# DVI-I.net
KiCad netlist of a schematic drawn in Altium Designer
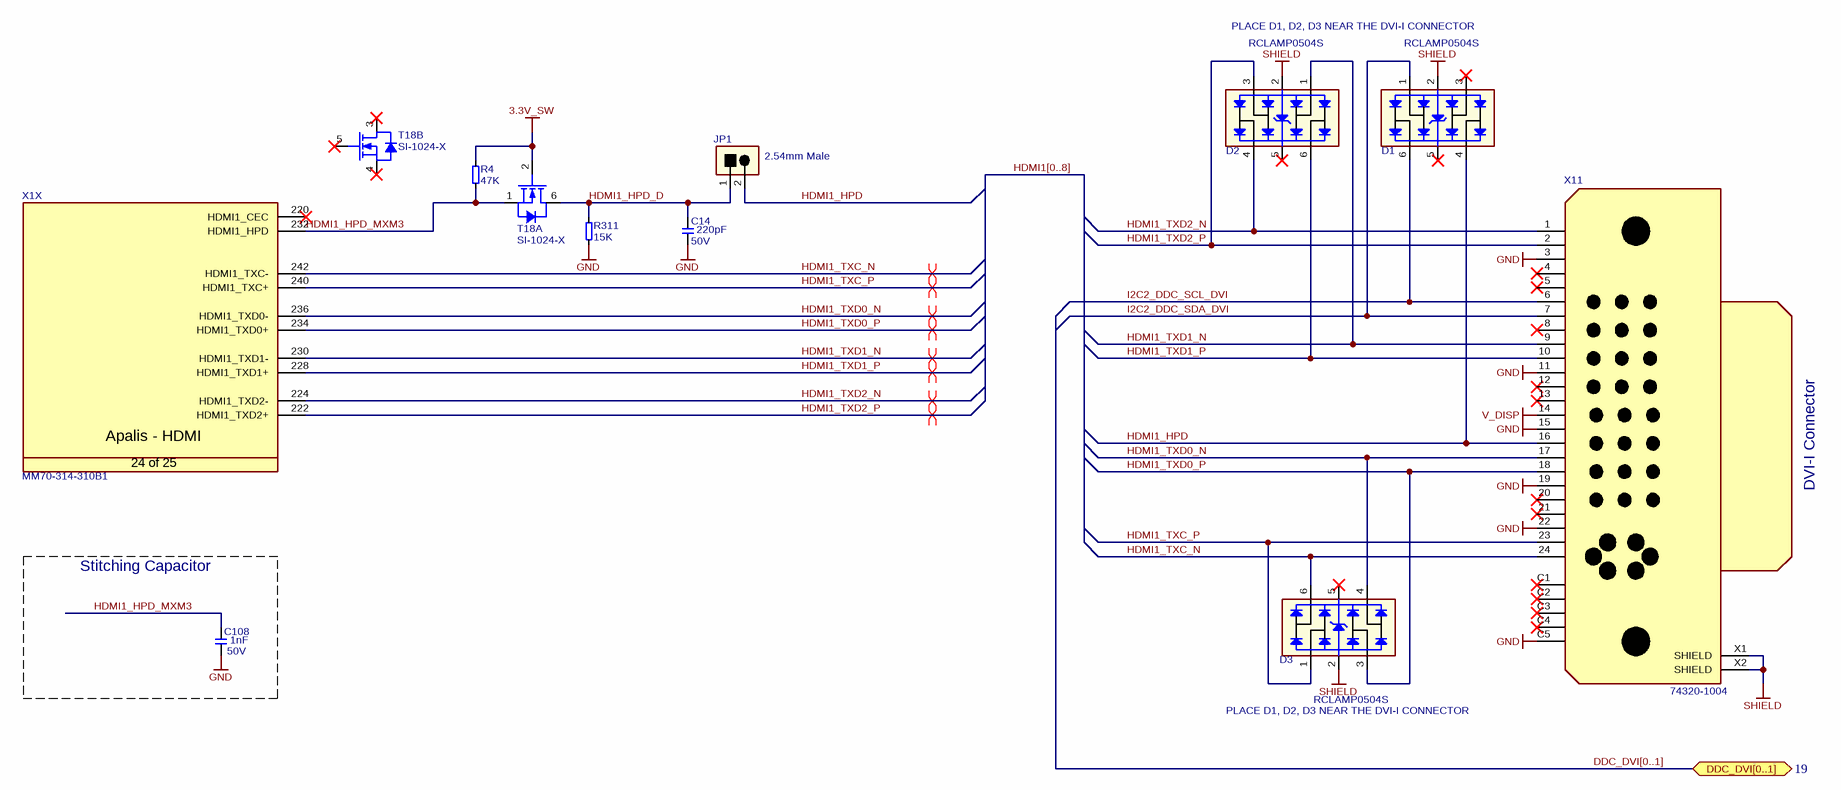
[diagram p0: DVI-I.SchDoc]

(export (version "E")
  (design (tool "Eeschema 10.0.6"))
  (components
    (comp (ref "C14")
      (value "220pF")
      (footprint "T_CAPC0603X33N")
      (description "Capacitor Ceramic X7R 220pF 50V 20% 0603")
      (fields (field (name "TOLERANCE") "20%") (field (name "RATING") "50V"))
      (libsource (lib "Apalis Evaluation Board") (part "C-X7R-220pF-50V-20%-0603"))
    )
    (comp (ref "C108")
      (value "1nF")
      (footprint "CAPC1005X60N")
      (description "Capacitor Ceramic X7R 1nF 50V 10% 0402")
      (fields (field (name "TOLERANCE") "10%") (field (name "RATING") "50V"))
      (libsource (lib "Apalis Evaluation Board") (part "C-X7R-1nF-50V-10%-0402"))
    )
    (comp (ref "D1")
      (value "RCLAMP0504S")
      (footprint "T_SOT95P285X90-6N")
      (description "TVS Array low cap")
      (fields (field (name "MANUFACTURER PART NO.") "RCLAMP0504S"))
      (libsource (lib "Apalis Evaluation Board") (part "D-Semtech-RClamp0504S"))
    )
    (comp (ref "D2")
      (value "RCLAMP0504S")
      (footprint "T_SOT95P285X90-6N")
      (description "TVS Array low cap")
      (fields (field (name "MANUFACTURER PART NO.") "RCLAMP0504S"))
      (libsource (lib "") (part "D-Semtech-RClamp0504S_1"))
    )
    (comp (ref "D3")
      (value "RCLAMP0504S")
      (footprint "T_SOT95P285X90-6N")
      (description "TVS Array low cap")
      (fields (field (name "MANUFACTURER PART NO.") "RCLAMP0504S"))
      (libsource (lib "") (part "D-Semtech-RClamp0504S_2"))
    )
    (comp (ref "JP1")
      (value "TSW-101-07-G-D")
      (footprint "T_Samtec_TSW-101-07-G-D")
      (description "Header male, 1x2 Pins, 2.54 mm pitch")
      (libsource (lib "Apalis Evaluation Board") (part "CON-Samtec-TSW-101-07-G-D"))
    )
    (comp (ref "R4")
      (value "47K")
      (footprint "T_RESC0603X30N")
      (description "Resistor 47 Kohm 63mW 5% 0603")
      (fields (field (name "TOLERANCE") "5%"))
      (libsource (lib "Apalis Evaluation Board") (part "R-47KR-63mW-5%-0603"))
    )
    (comp (ref "R311")
      (value "15K")
      (footprint "T_RESC0603X30N")
      (description "Resistor 15 Kohm 63mW 5% 0603")
      (fields (field (name "TOLERANCE") "5%"))
      (libsource (lib "Apalis Evaluation Board") (part "R-15KR-63mW-5%-0603"))
    )
    (comp (ref "T18")
      (value "T-Vishay-SI-1024X-N")
      (footprint "SOTFL50P160X60-6N")
      (description "Dual N-Channel 20V (D-S)  MOSFET")
      (fields (field (name "MANUFACTURER PART NO.") "SI-1024-X"))
      (libsource (lib "Apalis Evaluation Board") (part "T-Vishay-SI-1024X-N"))
    )
    (comp (ref "X1")
      (value "CON-JAE-MM70-314-310B1-314-0.5mm")
      (footprint "T_JAE_MM70-314-310B1")
      (description "MXM3 Connector")
      (fields (field (name "MANUFACTURER PART NO.") "MM70-314-310B1"))
      (libsource (lib "Apalis Evaluation Board") (part "CON-JAE-MM70-314-310B1-314-0.5mm"))
    )
    (comp (ref "X11")
      (value "CON-Molex-74320-1004-31")
      (footprint "T_MOLEX_74320-1004")
      (description "DVI Connector")
      (fields (field (name "MANUFACTURER PART NO.") "74320-1004"))
      (libsource (lib "Apalis Evaluation Board") (part "CON-Molex-74320-1004-31"))
    )
  )
  (nets
    (net (code "14") (name "/HDMI1_HPD") (class "Default")
      (node (ref "D1") (pin "4") (pinfunction "4_4") (pintype "power_in"))
      (node (ref "JP1") (pin "2") (pinfunction "2_2") (pintype "passive"))
      (node (ref "X11") (pin "16") (pinfunction "HOTPLUG_DETECT_16") (pintype "passive"))
    )
    (net (code "15") (name "/HDMI1_HPD_D") (class "Default")
      (node (ref "C14") (pin "1") (pinfunction "1_1") (pintype "passive"))
      (node (ref "JP1") (pin "1") (pinfunction "1_1") (pintype "passive"))
      (node (ref "R311") (pin "2") (pinfunction "2_2") (pintype "passive"))
      (node (ref "T18") (pin "6") (pinfunction "D_6") (pintype "passive"))
    )
    (net (code "16") (name "/HDMI1_HPD_MXM3") (class "Default")
      (node (ref "C108") (pin "2") (pinfunction "2_2") (pintype "passive"))
      (node (ref "R4") (pin "1") (pinfunction "1_1") (pintype "passive"))
      (node (ref "T18") (pin "1") (pinfunction "S_1") (pintype "passive"))
      (node (ref "X1") (pin "232") (pinfunction "HDMI1_HPD_232") (pintype "passive"))
    )
    (net (code "17") (name "/HDMI1_TXC_N") (class "Default")
      (node (ref "D3") (pin "6") (pinfunction "6_6") (pintype "power_in"))
      (node (ref "X1") (pin "242") (pinfunction "HDMI1_TXC-_242") (pintype "passive"))
      (node (ref "X11") (pin "24") (pinfunction "TMDS_CLK_N_24") (pintype "passive"))
    )
    (net (code "18") (name "/HDMI1_TXC_P") (class "Default")
      (node (ref "D3") (pin "1") (pinfunction "1_1") (pintype "power_in"))
      (node (ref "X1") (pin "240") (pinfunction "HDMI1_TXC+_240") (pintype "passive"))
      (node (ref "X11") (pin "23") (pinfunction "TMDS_CLK_P_23") (pintype "passive"))
    )
    (net (code "19") (name "/HDMI1_TXD0_N") (class "Default")
      (node (ref "D3") (pin "4") (pinfunction "4_4") (pintype "power_in"))
      (node (ref "X1") (pin "236") (pinfunction "HDMI1_TXD0-_236") (pintype "passive"))
      (node (ref "X11") (pin "17") (pinfunction "TMDS_DATA0_N_17") (pintype "passive"))
    )
    (net (code "20") (name "/HDMI1_TXD0_P") (class "Default")
      (node (ref "D3") (pin "3") (pinfunction "3_3") (pintype "power_in"))
      (node (ref "X1") (pin "234") (pinfunction "HDMI1_TXD0+_234") (pintype "passive"))
      (node (ref "X11") (pin "18") (pinfunction "TMDS_DATA0_P_18") (pintype "passive"))
    )
    (net (code "21") (name "/HDMI1_TXD1_N") (class "Default")
      (node (ref "D2") (pin "1") (pinfunction "1_1") (pintype "power_in"))
      (node (ref "X1") (pin "230") (pinfunction "HDMI1_TXD1-_230") (pintype "passive"))
      (node (ref "X11") (pin "9") (pinfunction "TMDS_DATA1_N_9") (pintype "passive"))
    )
    (net (code "22") (name "/HDMI1_TXD1_P") (class "Default")
      (node (ref "D2") (pin "6") (pinfunction "6_6") (pintype "power_in"))
      (node (ref "X1") (pin "228") (pinfunction "HDMI1_TXD1+_228") (pintype "passive"))
      (node (ref "X11") (pin "10") (pinfunction "TMDS_DATA1_P_10") (pintype "passive"))
    )
    (net (code "23") (name "/HDMI1_TXD2_N") (class "Default")
      (node (ref "D2") (pin "4") (pinfunction "4_4") (pintype "power_in"))
      (node (ref "X1") (pin "224") (pinfunction "HDMI1_TXD2-_224") (pintype "passive"))
      (node (ref "X11") (pin "1") (pinfunction "TMDS_DATA2_N_1") (pintype "passive"))
    )
    (net (code "24") (name "/HDMI1_TXD2_P") (class "Default")
      (node (ref "D2") (pin "3") (pinfunction "3_3") (pintype "power_in"))
      (node (ref "X1") (pin "222") (pinfunction "HDMI1_TXD2+_222") (pintype "passive"))
      (node (ref "X11") (pin "2") (pinfunction "TMDS_DATA2_P_2") (pintype "passive"))
    )
    (net (code "25") (name "/I2C2_DDC_SCL_DVI") (class "Default")
      (node (ref "D1") (pin "6") (pinfunction "6_6") (pintype "power_in"))
      (node (ref "X11") (pin "6") (pinfunction "DDC_CLK_6") (pintype "passive"))
    )
    (net (code "26") (name "/I2C2_DDC_SDA_DVI") (class "Default")
      (node (ref "D1") (pin "1") (pinfunction "1_1") (pintype "power_in"))
      (node (ref "X11") (pin "7") (pinfunction "DDC_DATA_7") (pintype "passive"))
    )
    (net (code "27") (name "3.3V_SW") (class "Default")
      (node (ref "R4") (pin "2") (pinfunction "2_2") (pintype "passive"))
      (node (ref "T18") (pin "2") (pinfunction "G_2") (pintype "passive"))
    )
    (net (code "28") (name "GND") (class "Default")
      (node (ref "C108") (pin "1") (pinfunction "1_1") (pintype "passive"))
      (node (ref "C14") (pin "2") (pinfunction "2_2") (pintype "passive"))
      (node (ref "R311") (pin "1") (pinfunction "1_1") (pintype "passive"))
      (node (ref "X11") (pin "11") (pinfunction "GND_11") (pintype "passive"))
      (node (ref "X11") (pin "15") (pinfunction "GND_15") (pintype "passive"))
      (node (ref "X11") (pin "19") (pinfunction "GND_19") (pintype "passive"))
      (node (ref "X11") (pin "22") (pinfunction "GND_22") (pintype "passive"))
      (node (ref "X11") (pin "3") (pinfunction "GND_3") (pintype "passive"))
      (node (ref "X11") (pin "C5") (pinfunction "GND_C5") (pintype "passive"))
    )
    (net (code "29") (name "SHIELD") (class "Default")
      (node (ref "D1") (pin "2") (pinfunction "2_2") (pintype "power_in"))
      (node (ref "D2") (pin "2") (pinfunction "2_2") (pintype "power_in"))
      (node (ref "D3") (pin "2") (pinfunction "2_2") (pintype "power_in"))
      (node (ref "X11") (pin "X1") (pinfunction "SHIELD_X1") (pintype "passive"))
      (node (ref "X11") (pin "X2") (pinfunction "SHIELD_X2") (pintype "passive"))
    )
    (net (code "30") (name "V_DISP") (class "Default")
      (node (ref "X11") (pin "14") (pinfunction "VDD_DVI_14") (pintype "passive"))
    )
    (net (code "31") (name "unconnected-(D1-Pad3)") (class "Default")
      (node (ref "D1") (pin "3") (pinfunction "3_3") (pintype "power_in+no_connect"))
    )
    (net (code "32") (name "unconnected-(D1-Pad5)") (class "Default")
      (node (ref "D1") (pin "5") (pinfunction "5_5") (pintype "power_in+no_connect"))
    )
    (net (code "33") (name "unconnected-(D2-Pad5)") (class "Default")
      (node (ref "D2") (pin "5") (pinfunction "5_5") (pintype "power_in+no_connect"))
    )
    (net (code "34") (name "unconnected-(D3-Pad5)") (class "Default")
      (node (ref "D3") (pin "5") (pinfunction "5_5") (pintype "power_in+no_connect"))
    )
    (net (code "35") (name "unconnected-(T18B-D-Pad3)") (class "Default")
      (node (ref "T18") (pin "3") (pinfunction "D_3") (pintype "passive+no_connect"))
    )
    (net (code "36") (name "unconnected-(T18B-G-Pad5)") (class "Default")
      (node (ref "T18") (pin "5") (pinfunction "G_5") (pintype "passive+no_connect"))
    )
    (net (code "37") (name "unconnected-(T18B-S-Pad4)") (class "Default")
      (node (ref "T18") (pin "4") (pinfunction "S_4") (pintype "passive+no_connect"))
    )
    (net (code "38") (name "unconnected-(X1X-HDMI1_CEC-Pad220)") (class "Default")
      (node (ref "X1") (pin "220") (pinfunction "HDMI1_CEC_220") (pintype "passive+no_connect"))
    )
    (net (code "39") (name "unconnected-(X11-CRT_BLUE-PadC3)") (class "Default")
      (node (ref "X11") (pin "C3") (pinfunction "CRT_BLUE_C3") (pintype "passive+no_connect"))
    )
    (net (code "40") (name "unconnected-(X11-CRT_GREEN-PadC2)") (class "Default")
      (node (ref "X11") (pin "C2") (pinfunction "CRT_GREEN_C2") (pintype "passive+no_connect"))
    )
    (net (code "41") (name "unconnected-(X11-CRT_HSYNC-PadC4)") (class "Default")
      (node (ref "X11") (pin "C4") (pinfunction "CRT_HSYNC_C4") (pintype "passive+no_connect"))
    )
    (net (code "42") (name "unconnected-(X11-CRT_RED-PadC1)") (class "Default")
      (node (ref "X11") (pin "C1") (pinfunction "CRT_RED_C1") (pintype "passive+no_connect"))
    )
    (net (code "43") (name "unconnected-(X11-CRT_VSYNC-Pad8)") (class "Default")
      (node (ref "X11") (pin "8") (pinfunction "CRT_VSYNC_8") (pintype "passive+no_connect"))
    )
    (net (code "44") (name "unconnected-(X11-TMDS_DATA3_N-Pad12)") (class "Default")
      (node (ref "X11") (pin "12") (pinfunction "TMDS_DATA3_N_12") (pintype "passive+no_connect"))
    )
    (net (code "45") (name "unconnected-(X11-TMDS_DATA3_P-Pad13)") (class "Default")
      (node (ref "X11") (pin "13") (pinfunction "TMDS_DATA3_P_13") (pintype "passive+no_connect"))
    )
    (net (code "46") (name "unconnected-(X11-TMDS_DATA4_N-Pad4)") (class "Default")
      (node (ref "X11") (pin "4") (pinfunction "TMDS_DATA4_N_4") (pintype "passive+no_connect"))
    )
    (net (code "47") (name "unconnected-(X11-TMDS_DATA4_P-Pad5)") (class "Default")
      (node (ref "X11") (pin "5") (pinfunction "TMDS_DATA4_P_5") (pintype "passive+no_connect"))
    )
    (net (code "48") (name "unconnected-(X11-TMDS_DATA5_N-Pad20)") (class "Default")
      (node (ref "X11") (pin "20") (pinfunction "TMDS_DATA5_N_20") (pintype "passive+no_connect"))
    )
    (net (code "49") (name "unconnected-(X11-TMDS_DATA5_P-Pad21)") (class "Default")
      (node (ref "X11") (pin "21") (pinfunction "TMDS_DATA5_P_21") (pintype "passive+no_connect"))
    )
  )
)
